# usb.net
KiCad netlist of a schematic drawn in Altium Designer
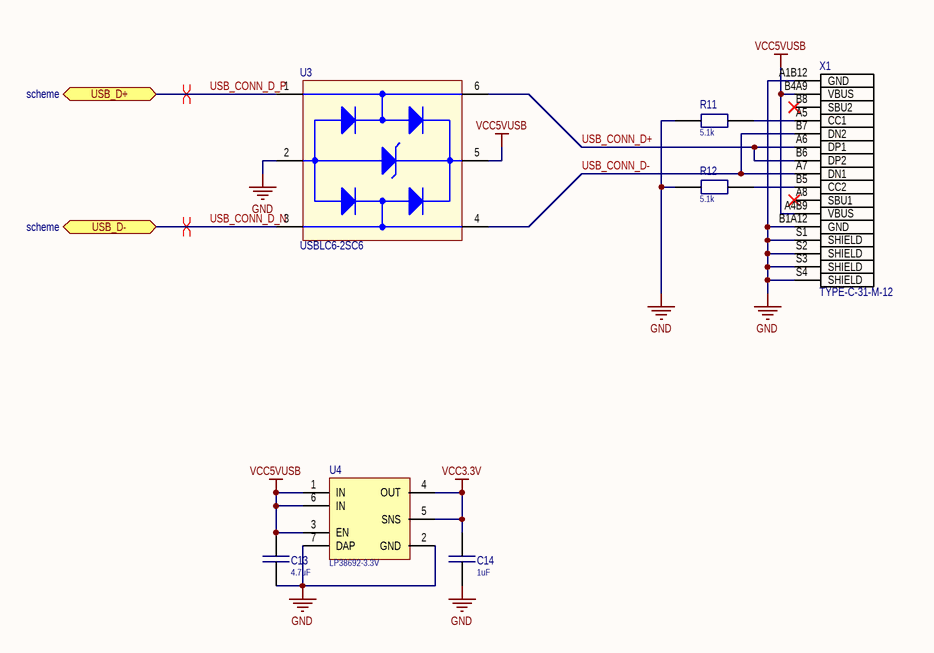
[diagram p0: usb.SchDoc]

(export (version "E")
  (design (tool "Eeschema 10.0.6"))
  (components
    (comp (ref "C13")
      (value "4.7uF")
      (footprint "C_0603")
      (description "Capacitor")
      (fields (field (name "PART NUMBER") "CC0603KRX5R6BB475"))
      (libsource (lib "capacitors") (part "CAP_SMD"))
    )
    (comp (ref "C14")
      (value "1uF")
      (footprint "C_0603")
      (description "Capacitor")
      (fields (field (name "PART NUMBER") "CC0603ZRY5V7BB105"))
      (libsource (lib "capacitors") (part "CAP_SMD"))
    )
    (comp (ref "R11")
      (value "5.1k")
      (footprint "R_0603")
      (description "Resistor")
      (fields (field (name "PART NUMBER") "RC0603FR-075K1L"))
      (libsource (lib "resistors") (part "RES_SMD"))
    )
    (comp (ref "R12")
      (value "5.1k")
      (footprint "R_0603")
      (description "Resistor")
      (fields (field (name "PART NUMBER") "RC0603FR-075K1L"))
      (libsource (lib "resistors") (part "RES_SMD"))
    )
    (comp (ref "U3")
      (value "USBLC6-2SC6")
      (footprint "diode:SOT95P280X145-6N")
      (description "17V Clamp 5A (8/20Âµs) Ipp Tvs Diode Surface Mount SOT-23-6")
      (fields (field (name "MF") "STMicroelectronics"))
      (libsource (lib "diode") (part "USBLC6-2SC6"))
    )
    (comp (ref "U4")
      (value "LP38692-3.3V")
      (footprint "WSON-6")
      (description "LP38690, LP38692 1-A LDO CMOS Linear Regulators  Stable with Ceramic Output Capacitors")
      (libsource (lib "AX_Altium_v2.3") (part "LP38692"))
    )
    (comp (ref "X1")
      (value "TYPE-C-31-M-12")
      (footprint "connectors_socets:HRO_TYPE-C-31-M-12")
      (description "USB Connectors 24 Receptacle 1 8.94*7.3mm RoHS")
      (libsource (lib "connectors_socets") (part "TYPE-C-31-M-12"))
    )
  )
  (nets
    (net (code "1") (name "/USB_CONN_D+") (class "Default")
      (node (ref "U3") (pin "6") (pinfunction "I/O1_OUT_6") (pintype "passive"))
      (node (ref "X1") (pin "A6") (pinfunction "DP1_A6") (pintype "passive"))
      (node (ref "X1") (pin "B6") (pinfunction "DP2_B6") (pintype "passive"))
    )
    (net (code "2") (name "/USB_CONN_D-") (class "Default")
      (node (ref "U3") (pin "4") (pinfunction "I/O2_OUT_4") (pintype "passive"))
      (node (ref "X1") (pin "A7") (pinfunction "DN1_A7") (pintype "passive"))
      (node (ref "X1") (pin "B7") (pinfunction "DN2_B7") (pintype "passive"))
    )
    (net (code "3") (name "/USB_CONN_D_N") (class "Default")
      (node (ref "U3") (pin "3") (pinfunction "I/O2_IN_3") (pintype "passive"))
    )
    (net (code "4") (name "/USB_CONN_D_P") (class "Default")
      (node (ref "U3") (pin "1") (pinfunction "I/O1_IN_1") (pintype "passive"))
    )
    (net (code "5") (name "GND") (class "Default")
      (node (ref "C13") (pin "1") (pinfunction "1_1") (pintype "passive"))
      (node (ref "C14") (pin "1") (pinfunction "1_1") (pintype "passive"))
      (node (ref "R11") (pin "1") (pinfunction "1_1") (pintype "passive"))
      (node (ref "R12") (pin "1") (pinfunction "1_1") (pintype "passive"))
      (node (ref "U3") (pin "2") (pinfunction "GND_2") (pintype "passive"))
      (node (ref "U4") (pin "2") (pinfunction "GND_2") (pintype "passive"))
      (node (ref "U4") (pin "7") (pinfunction "DAP_7") (pintype "passive"))
      (node (ref "X1") (pin "A1B12") (pinfunction "GND_A1B12") (pintype "passive"))
      (node (ref "X1") (pin "B1A12") (pinfunction "GND_B1A12") (pintype "passive"))
      (node (ref "X1") (pin "S1") (pinfunction "SHIELD_S1") (pintype "passive"))
      (node (ref "X1") (pin "S2") (pinfunction "SHIELD_S2") (pintype "passive"))
      (node (ref "X1") (pin "S3") (pinfunction "SHIELD_S3") (pintype "passive"))
      (node (ref "X1") (pin "S4") (pinfunction "SHIELD_S4") (pintype "passive"))
    )
    (net (code "6") (name "Net-(X1-CC1)") (class "Default")
      (node (ref "R11") (pin "2") (pinfunction "2_2") (pintype "passive"))
      (node (ref "X1") (pin "A5") (pinfunction "CC1_A5") (pintype "passive"))
    )
    (net (code "7") (name "Net-(X1-CC2)") (class "Default")
      (node (ref "R12") (pin "2") (pinfunction "2_2") (pintype "passive"))
      (node (ref "X1") (pin "B5") (pinfunction "CC2_B5") (pintype "passive"))
    )
    (net (code "8") (name "VCC3.3V") (class "Default")
      (node (ref "C14") (pin "2") (pinfunction "2_2") (pintype "passive"))
      (node (ref "U4") (pin "4") (pinfunction "OUT_4") (pintype "passive"))
      (node (ref "U4") (pin "5") (pinfunction "SNS_5") (pintype "passive"))
    )
    (net (code "9") (name "VCC5VUSB") (class "Default")
      (node (ref "C13") (pin "2") (pinfunction "2_2") (pintype "passive"))
      (node (ref "U3") (pin "5") (pinfunction "VBUS_5") (pintype "passive"))
      (node (ref "U4") (pin "1") (pinfunction "IN_1") (pintype "passive"))
      (node (ref "U4") (pin "3") (pinfunction "EN_3") (pintype "passive"))
      (node (ref "U4") (pin "6") (pinfunction "IN_6") (pintype "passive"))
      (node (ref "X1") (pin "A4B9") (pinfunction "VBUS_A4B9") (pintype "passive"))
      (node (ref "X1") (pin "B4A9") (pinfunction "VBUS_B4A9") (pintype "passive"))
    )
    (net (code "10") (name "unconnected-(X1-SBU1-PadA8)") (class "Default")
      (node (ref "X1") (pin "A8") (pinfunction "SBU1_A8") (pintype "passive+no_connect"))
    )
    (net (code "11") (name "unconnected-(X1-SBU2-PadB8)") (class "Default")
      (node (ref "X1") (pin "B8") (pinfunction "SBU2_B8") (pintype "passive+no_connect"))
    )
  )
)
